# button.net
KiCad netlist of a schematic drawn in EAGLE
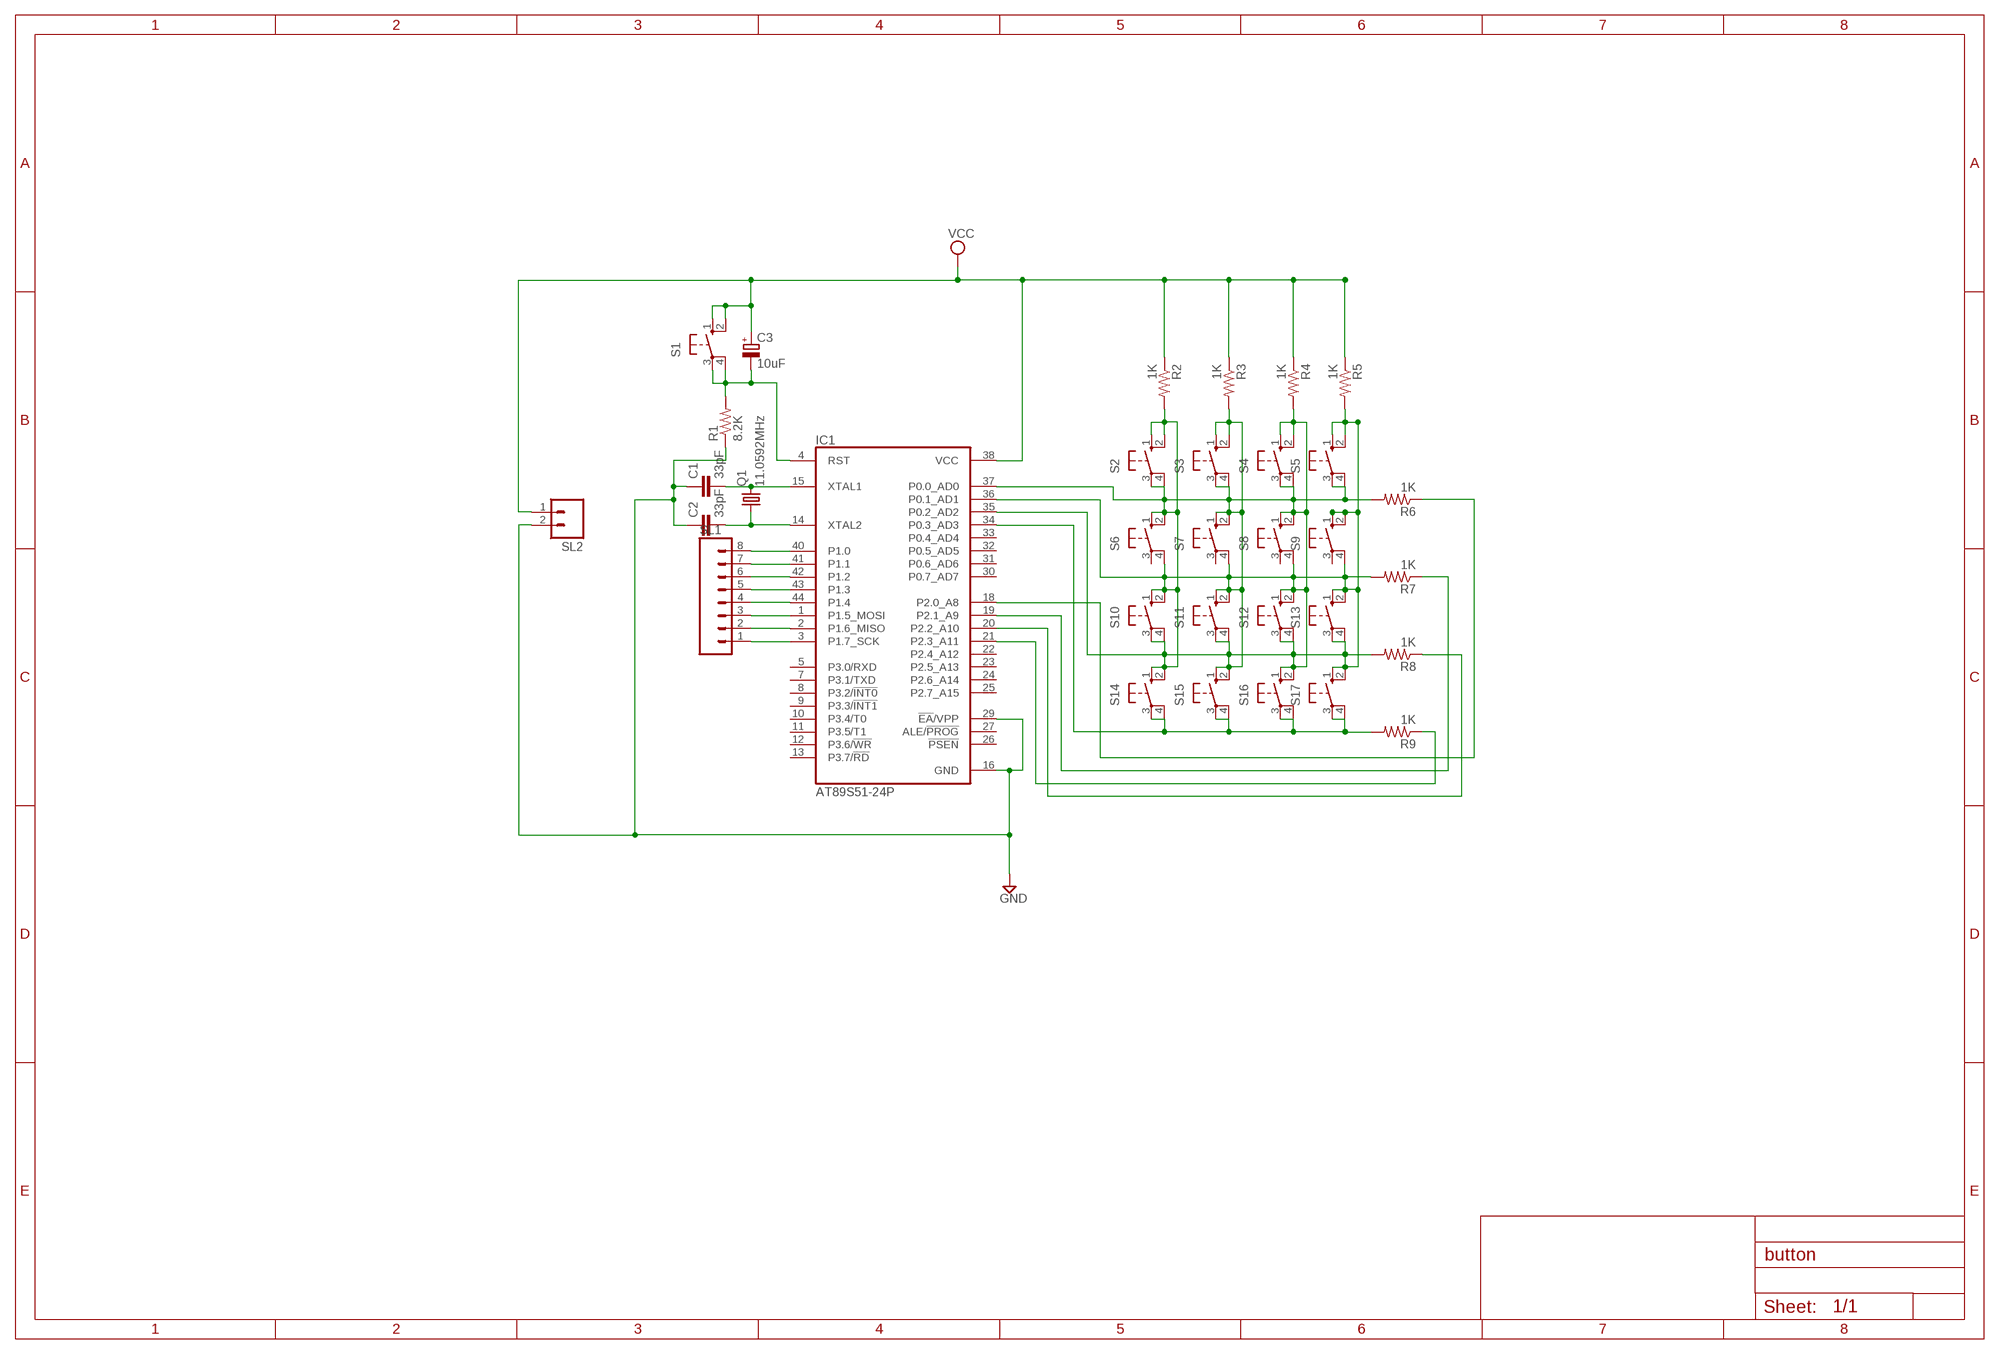
[diagram p0: schematic, sheet 1]

(export (version "E")
  (design (tool "Eeschema 10.0.6"))
  (components
    (comp (ref "C1")
      (value "33pF")
      (footprint "eagle-import:C1206K")
      (libsource (lib "eagle-import") (part "C-EUC1206K"))
    )
    (comp (ref "C2")
      (value "33pF")
      (footprint "eagle-import:C1206K")
      (libsource (lib "eagle-import") (part "C-EUC1206K"))
    )
    (comp (ref "C3")
      (value "10uF")
      (footprint "eagle-import:140CLH-1010")
      (libsource (lib "eagle-import") (part "CPOL-EU140CLH-1010"))
    )
    (comp (ref "IC1")
      (value "AT89S51-24P")
      (footprint "eagle-import:TQFP44")
      (libsource (lib "eagle-import") (part "AT89S51P-24"))
    )
    (comp (ref "Q1")
      (value "11.0592MHz")
      (footprint "eagle-import:TC26V")
      (libsource (lib "eagle-import") (part "CRYSTALTC26V"))
    )
    (comp (ref "R1")
      (value "8.2K")
      (footprint "eagle-import:R1206")
      (libsource (lib "eagle-import") (part "R-US_R1206"))
    )
    (comp (ref "R2")
      (value "1K")
      (footprint "eagle-import:M1206")
      (libsource (lib "eagle-import") (part "R-US_M1206"))
    )
    (comp (ref "R3")
      (value "1K")
      (footprint "eagle-import:M1206")
      (libsource (lib "eagle-import") (part "R-US_M1206"))
    )
    (comp (ref "R4")
      (value "1K")
      (footprint "eagle-import:M1206")
      (libsource (lib "eagle-import") (part "R-US_M1206"))
    )
    (comp (ref "R5")
      (value "1K")
      (footprint "eagle-import:M1206")
      (libsource (lib "eagle-import") (part "R-US_M1206"))
    )
    (comp (ref "R6")
      (value "1K")
      (footprint "eagle-import:M1206")
      (libsource (lib "eagle-import") (part "R-US_M1206"))
    )
    (comp (ref "R7")
      (value "1K")
      (footprint "eagle-import:M1206")
      (libsource (lib "eagle-import") (part "R-US_M1206"))
    )
    (comp (ref "R8")
      (value "1K")
      (footprint "eagle-import:M1206")
      (libsource (lib "eagle-import") (part "R-US_M1206"))
    )
    (comp (ref "R9")
      (value "1K")
      (footprint "eagle-import:M1206")
      (libsource (lib "eagle-import") (part "R-US_M1206"))
    )
    (comp (ref "S1")
      (value "10-XX")
      (footprint "eagle-import:B3F-10XX")
      (fields (field (name "MPN") "B3F-1000"))
      (libsource (lib "eagle-import") (part "10-XX"))
    )
    (comp (ref "S2")
      (value "10-XX")
      (footprint "eagle-import:B3F-10XX")
      (fields (field (name "MPN") "B3F-1000"))
      (libsource (lib "eagle-import") (part "10-XX"))
    )
    (comp (ref "S3")
      (value "10-XX")
      (footprint "eagle-import:B3F-10XX")
      (fields (field (name "MPN") "B3F-1000"))
      (libsource (lib "eagle-import") (part "10-XX"))
    )
    (comp (ref "S4")
      (value "10-XX")
      (footprint "eagle-import:B3F-10XX")
      (fields (field (name "MPN") "B3F-1000"))
      (libsource (lib "eagle-import") (part "10-XX"))
    )
    (comp (ref "S5")
      (value "10-XX")
      (footprint "eagle-import:B3F-10XX")
      (fields (field (name "MPN") "B3F-1000"))
      (libsource (lib "eagle-import") (part "10-XX"))
    )
    (comp (ref "S6")
      (value "10-XX")
      (footprint "eagle-import:B3F-10XX")
      (fields (field (name "MPN") "B3F-1000"))
      (libsource (lib "eagle-import") (part "10-XX"))
    )
    (comp (ref "S7")
      (value "10-XX")
      (footprint "eagle-import:B3F-10XX")
      (fields (field (name "MPN") "B3F-1000"))
      (libsource (lib "eagle-import") (part "10-XX"))
    )
    (comp (ref "S8")
      (value "10-XX")
      (footprint "eagle-import:B3F-10XX")
      (fields (field (name "MPN") "B3F-1000"))
      (libsource (lib "eagle-import") (part "10-XX"))
    )
    (comp (ref "S9")
      (value "10-XX")
      (footprint "eagle-import:B3F-10XX")
      (fields (field (name "MPN") "B3F-1000"))
      (libsource (lib "eagle-import") (part "10-XX"))
    )
    (comp (ref "S10")
      (value "10-XX")
      (footprint "eagle-import:B3F-10XX")
      (fields (field (name "MPN") "B3F-1000"))
      (libsource (lib "eagle-import") (part "10-XX"))
    )
    (comp (ref "S11")
      (value "10-XX")
      (footprint "eagle-import:B3F-10XX")
      (fields (field (name "MPN") "B3F-1000"))
      (libsource (lib "eagle-import") (part "10-XX"))
    )
    (comp (ref "S12")
      (value "10-XX")
      (footprint "eagle-import:B3F-10XX")
      (fields (field (name "MPN") "B3F-1000"))
      (libsource (lib "eagle-import") (part "10-XX"))
    )
    (comp (ref "S13")
      (value "10-XX")
      (footprint "eagle-import:B3F-10XX")
      (fields (field (name "MPN") "B3F-1000"))
      (libsource (lib "eagle-import") (part "10-XX"))
    )
    (comp (ref "S14")
      (value "10-XX")
      (footprint "eagle-import:B3F-10XX")
      (fields (field (name "MPN") "B3F-1000"))
      (libsource (lib "eagle-import") (part "10-XX"))
    )
    (comp (ref "S15")
      (value "10-XX")
      (footprint "eagle-import:B3F-10XX")
      (fields (field (name "MPN") "B3F-1000"))
      (libsource (lib "eagle-import") (part "10-XX"))
    )
    (comp (ref "S16")
      (value "10-XX")
      (footprint "eagle-import:B3F-10XX")
      (fields (field (name "MPN") "B3F-1000"))
      (libsource (lib "eagle-import") (part "10-XX"))
    )
    (comp (ref "S17")
      (value "10-XX")
      (footprint "eagle-import:B3F-10XX")
      (fields (field (name "MPN") "B3F-1000"))
      (libsource (lib "eagle-import") (part "10-XX"))
    )
    (comp (ref "SL1")
      (value "MA08")
      (footprint "eagle-import:08PA")
      (libsource (lib "eagle-import") (part "MA08"))
    )
    (comp (ref "SL2")
      (value "MA02")
      (footprint "eagle-import:02PA")
      (libsource (lib "eagle-import") (part "MA02"))
    )
  )
  (nets
    (net (code "1") (name "GND") (class "Default")
      (node (ref "C1") (pin "1") (pinfunction "1_1") (pintype "passive"))
      (node (ref "C2") (pin "1") (pinfunction "1_1") (pintype "passive"))
      (node (ref "IC1") (pin "16") (pinfunction "GND_16") (pintype "power_in"))
      (node (ref "IC1") (pin "29") (pinfunction "~{EA}/VPP_29") (pintype "input"))
      (node (ref "R1") (pin "1") (pinfunction "1_1") (pintype "passive"))
      (node (ref "SL2") (pin "2") (pinfunction "2_2") (pintype "passive"))
    )
    (net (code "2") (name "Net-(IC1A-P0.0_AD0)") (class "Default")
      (node (ref "IC1") (pin "35") (pinfunction "P0.2_AD2_35") (pintype "bidirectional"))
      (node (ref "IC1") (pin "36") (pinfunction "P0.1_AD1_36") (pintype "bidirectional"))
      (node (ref "IC1") (pin "37") (pinfunction "P0.0_AD0_37") (pintype "bidirectional"))
      (node (ref "R2") (pin "2") (pinfunction "2_2") (pintype "passive"))
      (node (ref "R3") (pin "2") (pinfunction "2_2") (pintype "passive"))
      (node (ref "R4") (pin "2") (pinfunction "2_2") (pintype "passive"))
      (node (ref "R5") (pin "2") (pinfunction "2_2") (pintype "passive"))
      (node (ref "R6") (pin "2") (pinfunction "2_2") (pintype "passive"))
      (node (ref "R7") (pin "2") (pinfunction "2_2") (pintype "passive"))
      (node (ref "R8") (pin "2") (pinfunction "2_2") (pintype "passive"))
      (node (ref "S10") (pin "1") (pinfunction "S_1") (pintype "passive"))
      (node (ref "S10") (pin "2") (pinfunction "S1_2") (pintype "passive"))
      (node (ref "S10") (pin "3") (pinfunction "P_3") (pintype "passive"))
      (node (ref "S10") (pin "4") (pinfunction "P1_4") (pintype "passive"))
      (node (ref "S11") (pin "1") (pinfunction "S_1") (pintype "passive"))
      (node (ref "S11") (pin "2") (pinfunction "S1_2") (pintype "passive"))
      (node (ref "S11") (pin "3") (pinfunction "P_3") (pintype "passive"))
      (node (ref "S11") (pin "4") (pinfunction "P1_4") (pintype "passive"))
      (node (ref "S12") (pin "1") (pinfunction "S_1") (pintype "passive"))
      (node (ref "S12") (pin "2") (pinfunction "S1_2") (pintype "passive"))
      (node (ref "S12") (pin "3") (pinfunction "P_3") (pintype "passive"))
      (node (ref "S12") (pin "4") (pinfunction "P1_4") (pintype "passive"))
      (node (ref "S13") (pin "1") (pinfunction "S_1") (pintype "passive"))
      (node (ref "S13") (pin "2") (pinfunction "S1_2") (pintype "passive"))
      (node (ref "S13") (pin "3") (pinfunction "P_3") (pintype "passive"))
      (node (ref "S13") (pin "4") (pinfunction "P1_4") (pintype "passive"))
      (node (ref "S14") (pin "1") (pinfunction "S_1") (pintype "passive"))
      (node (ref "S14") (pin "2") (pinfunction "S1_2") (pintype "passive"))
      (node (ref "S15") (pin "1") (pinfunction "S_1") (pintype "passive"))
      (node (ref "S15") (pin "2") (pinfunction "S1_2") (pintype "passive"))
      (node (ref "S16") (pin "1") (pinfunction "S_1") (pintype "passive"))
      (node (ref "S16") (pin "2") (pinfunction "S1_2") (pintype "passive"))
      (node (ref "S17") (pin "1") (pinfunction "S_1") (pintype "passive"))
      (node (ref "S17") (pin "2") (pinfunction "S1_2") (pintype "passive"))
      (node (ref "S2") (pin "1") (pinfunction "S_1") (pintype "passive"))
      (node (ref "S2") (pin "2") (pinfunction "S1_2") (pintype "passive"))
      (node (ref "S2") (pin "3") (pinfunction "P_3") (pintype "passive"))
      (node (ref "S2") (pin "4") (pinfunction "P1_4") (pintype "passive"))
      (node (ref "S3") (pin "1") (pinfunction "S_1") (pintype "passive"))
      (node (ref "S3") (pin "2") (pinfunction "S1_2") (pintype "passive"))
      (node (ref "S3") (pin "3") (pinfunction "P_3") (pintype "passive"))
      (node (ref "S3") (pin "4") (pinfunction "P1_4") (pintype "passive"))
      (node (ref "S4") (pin "1") (pinfunction "S_1") (pintype "passive"))
      (node (ref "S4") (pin "2") (pinfunction "S1_2") (pintype "passive"))
      (node (ref "S4") (pin "3") (pinfunction "P_3") (pintype "passive"))
      (node (ref "S4") (pin "4") (pinfunction "P1_4") (pintype "passive"))
      (node (ref "S5") (pin "1") (pinfunction "S_1") (pintype "passive"))
      (node (ref "S5") (pin "2") (pinfunction "S1_2") (pintype "passive"))
      (node (ref "S5") (pin "3") (pinfunction "P_3") (pintype "passive"))
      (node (ref "S5") (pin "4") (pinfunction "P1_4") (pintype "passive"))
      (node (ref "S6") (pin "1") (pinfunction "S_1") (pintype "passive"))
      (node (ref "S6") (pin "2") (pinfunction "S1_2") (pintype "passive"))
      (node (ref "S6") (pin "4") (pinfunction "P1_4") (pintype "passive"))
      (node (ref "S7") (pin "1") (pinfunction "S_1") (pintype "passive"))
      (node (ref "S7") (pin "2") (pinfunction "S1_2") (pintype "passive"))
      (node (ref "S7") (pin "4") (pinfunction "P1_4") (pintype "passive"))
      (node (ref "S8") (pin "1") (pinfunction "S_1") (pintype "passive"))
      (node (ref "S8") (pin "2") (pinfunction "S1_2") (pintype "passive"))
      (node (ref "S8") (pin "4") (pinfunction "P1_4") (pintype "passive"))
      (node (ref "S9") (pin "1") (pinfunction "S_1") (pintype "passive"))
      (node (ref "S9") (pin "2") (pinfunction "S1_2") (pintype "passive"))
      (node (ref "S9") (pin "4") (pinfunction "P1_4") (pintype "passive"))
    )
    (net (code "3") (name "Net-(IC1A-P0.3_AD3)") (class "Default")
      (node (ref "IC1") (pin "34") (pinfunction "P0.3_AD3_34") (pintype "bidirectional"))
      (node (ref "R9") (pin "2") (pinfunction "2_2") (pintype "passive"))
      (node (ref "S14") (pin "3") (pinfunction "P_3") (pintype "passive"))
      (node (ref "S14") (pin "4") (pinfunction "P1_4") (pintype "passive"))
      (node (ref "S15") (pin "3") (pinfunction "P_3") (pintype "passive"))
      (node (ref "S15") (pin "4") (pinfunction "P1_4") (pintype "passive"))
      (node (ref "S16") (pin "3") (pinfunction "P_3") (pintype "passive"))
      (node (ref "S16") (pin "4") (pinfunction "P1_4") (pintype "passive"))
      (node (ref "S17") (pin "3") (pinfunction "P_3") (pintype "passive"))
      (node (ref "S17") (pin "4") (pinfunction "P1_4") (pintype "passive"))
    )
    (net (code "4") (name "Net-(IC1A-P1.0)") (class "Default")
      (node (ref "IC1") (pin "40") (pinfunction "P1.0_40") (pintype "bidirectional"))
      (node (ref "SL1") (pin "8") (pinfunction "8_8") (pintype "passive"))
    )
    (net (code "5") (name "Net-(IC1A-P1.1)") (class "Default")
      (node (ref "IC1") (pin "41") (pinfunction "P1.1_41") (pintype "bidirectional"))
      (node (ref "SL1") (pin "7") (pinfunction "7_7") (pintype "passive"))
    )
    (net (code "6") (name "Net-(IC1A-P1.2)") (class "Default")
      (node (ref "IC1") (pin "42") (pinfunction "P1.2_42") (pintype "bidirectional"))
      (node (ref "SL1") (pin "6") (pinfunction "6_6") (pintype "passive"))
    )
    (net (code "7") (name "Net-(IC1A-P1.3)") (class "Default")
      (node (ref "IC1") (pin "43") (pinfunction "P1.3_43") (pintype "bidirectional"))
      (node (ref "SL1") (pin "5") (pinfunction "5_5") (pintype "passive"))
    )
    (net (code "8") (name "Net-(IC1A-P1.4)") (class "Default")
      (node (ref "IC1") (pin "44") (pinfunction "P1.4_44") (pintype "bidirectional"))
      (node (ref "SL1") (pin "4") (pinfunction "4_4") (pintype "passive"))
    )
    (net (code "9") (name "Net-(IC1A-P1.5_MOSI)") (class "Default")
      (node (ref "IC1") (pin "1") (pinfunction "P1.5_MOSI_1") (pintype "bidirectional"))
      (node (ref "SL1") (pin "3") (pinfunction "3_3") (pintype "passive"))
    )
    (net (code "10") (name "Net-(IC1A-P1.6_MISO)") (class "Default")
      (node (ref "IC1") (pin "2") (pinfunction "P1.6_MISO_2") (pintype "bidirectional"))
      (node (ref "SL1") (pin "2") (pinfunction "2_2") (pintype "passive"))
    )
    (net (code "11") (name "Net-(IC1A-P1.7_SCK)") (class "Default")
      (node (ref "IC1") (pin "3") (pinfunction "P1.7_SCK_3") (pintype "bidirectional"))
      (node (ref "SL1") (pin "1") (pinfunction "1_1") (pintype "passive"))
    )
    (net (code "12") (name "Net-(IC1A-P2.0_A8)") (class "Default")
      (node (ref "IC1") (pin "18") (pinfunction "P2.0_A8_18") (pintype "bidirectional"))
      (node (ref "R6") (pin "1") (pinfunction "1_1") (pintype "passive"))
    )
    (net (code "13") (name "Net-(IC1A-P2.1_A9)") (class "Default")
      (node (ref "IC1") (pin "19") (pinfunction "P2.1_A9_19") (pintype "bidirectional"))
      (node (ref "R7") (pin "1") (pinfunction "1_1") (pintype "passive"))
    )
    (net (code "14") (name "Net-(IC1A-P2.2_A10)") (class "Default")
      (node (ref "IC1") (pin "20") (pinfunction "P2.2_A10_20") (pintype "bidirectional"))
      (node (ref "R8") (pin "1") (pinfunction "1_1") (pintype "passive"))
    )
    (net (code "15") (name "Net-(IC1A-P2.3_A11)") (class "Default")
      (node (ref "IC1") (pin "21") (pinfunction "P2.3_A11_21") (pintype "bidirectional"))
      (node (ref "R9") (pin "1") (pinfunction "1_1") (pintype "passive"))
    )
    (net (code "16") (name "Net-(IC1A-RST)") (class "Default")
      (node (ref "C3") (pin "-") (pinfunction "-_-") (pintype "passive"))
      (node (ref "IC1") (pin "4") (pinfunction "RST_4") (pintype "input"))
      (node (ref "R1") (pin "2") (pinfunction "2_2") (pintype "passive"))
      (node (ref "S1") (pin "3") (pinfunction "P_3") (pintype "passive"))
      (node (ref "S1") (pin "4") (pinfunction "P1_4") (pintype "passive"))
    )
    (net (code "17") (name "Net-(IC1A-XTAL1)") (class "Default")
      (node (ref "C1") (pin "2") (pinfunction "2_2") (pintype "passive"))
      (node (ref "IC1") (pin "15") (pinfunction "XTAL1_15") (pintype "input"))
      (node (ref "Q1") (pin "2") (pinfunction "2_2") (pintype "passive"))
    )
    (net (code "18") (name "Net-(IC1A-XTAL2)") (class "Default")
      (node (ref "C2") (pin "2") (pinfunction "2_2") (pintype "passive"))
      (node (ref "IC1") (pin "14") (pinfunction "XTAL2_14") (pintype "input"))
      (node (ref "Q1") (pin "1") (pinfunction "1_1") (pintype "passive"))
    )
    (net (code "19") (name "VCC") (class "Default")
      (node (ref "C3") (pin "+") (pinfunction "+_+") (pintype "passive"))
      (node (ref "IC1") (pin "38") (pinfunction "VCC_38") (pintype "power_in"))
      (node (ref "R2") (pin "1") (pinfunction "1_1") (pintype "passive"))
      (node (ref "R3") (pin "1") (pinfunction "1_1") (pintype "passive"))
      (node (ref "R4") (pin "1") (pinfunction "1_1") (pintype "passive"))
      (node (ref "R5") (pin "1") (pinfunction "1_1") (pintype "passive"))
      (node (ref "S1") (pin "1") (pinfunction "S_1") (pintype "passive"))
      (node (ref "S1") (pin "2") (pinfunction "S1_2") (pintype "passive"))
      (node (ref "SL2") (pin "1") (pinfunction "1_1") (pintype "passive"))
    )
    (net (code "20") (name "unconnected-(IC1A-ALE{slash}~{PROG}-Pad27)") (class "Default")
      (node (ref "IC1") (pin "27") (pinfunction "ALE/~{PROG}_27") (pintype "output"))
    )
    (net (code "21") (name "unconnected-(IC1A-P0.4_AD4-Pad33)") (class "Default")
      (node (ref "IC1") (pin "33") (pinfunction "P0.4_AD4_33") (pintype "bidirectional"))
    )
    (net (code "22") (name "unconnected-(IC1A-P0.5_AD5-Pad32)") (class "Default")
      (node (ref "IC1") (pin "32") (pinfunction "P0.5_AD5_32") (pintype "bidirectional"))
    )
    (net (code "23") (name "unconnected-(IC1A-P0.6_AD6-Pad31)") (class "Default")
      (node (ref "IC1") (pin "31") (pinfunction "P0.6_AD6_31") (pintype "bidirectional"))
    )
    (net (code "24") (name "unconnected-(IC1A-P0.7_AD7-Pad30)") (class "Default")
      (node (ref "IC1") (pin "30") (pinfunction "P0.7_AD7_30") (pintype "bidirectional"))
    )
    (net (code "25") (name "unconnected-(IC1A-P2.4_A12-Pad22)") (class "Default")
      (node (ref "IC1") (pin "22") (pinfunction "P2.4_A12_22") (pintype "bidirectional"))
    )
    (net (code "26") (name "unconnected-(IC1A-P2.5_A13-Pad23)") (class "Default")
      (node (ref "IC1") (pin "23") (pinfunction "P2.5_A13_23") (pintype "bidirectional"))
    )
    (net (code "27") (name "unconnected-(IC1A-P2.6_A14-Pad24)") (class "Default")
      (node (ref "IC1") (pin "24") (pinfunction "P2.6_A14_24") (pintype "bidirectional"))
    )
    (net (code "28") (name "unconnected-(IC1A-P2.7_A15-Pad25)") (class "Default")
      (node (ref "IC1") (pin "25") (pinfunction "P2.7_A15_25") (pintype "bidirectional"))
    )
    (net (code "29") (name "unconnected-(IC1A-P3.0{slash}RXD-Pad5)") (class "Default")
      (node (ref "IC1") (pin "5") (pinfunction "P3.0/RXD_5") (pintype "bidirectional"))
    )
    (net (code "30") (name "unconnected-(IC1A-P3.1{slash}TXD-Pad7)") (class "Default")
      (node (ref "IC1") (pin "7") (pinfunction "P3.1/TXD_7") (pintype "bidirectional"))
    )
    (net (code "31") (name "unconnected-(IC1A-P3.2{slash}~{INT0}-Pad8)") (class "Default")
      (node (ref "IC1") (pin "8") (pinfunction "P3.2/~{INT0}_8") (pintype "bidirectional"))
    )
    (net (code "32") (name "unconnected-(IC1A-P3.3{slash}~{INT1}-Pad9)") (class "Default")
      (node (ref "IC1") (pin "9") (pinfunction "P3.3/~{INT1}_9") (pintype "bidirectional"))
    )
    (net (code "33") (name "unconnected-(IC1A-P3.4{slash}T0-Pad10)") (class "Default")
      (node (ref "IC1") (pin "10") (pinfunction "P3.4/T0_10") (pintype "bidirectional"))
    )
    (net (code "34") (name "unconnected-(IC1A-P3.5{slash}T1-Pad11)") (class "Default")
      (node (ref "IC1") (pin "11") (pinfunction "P3.5/T1_11") (pintype "bidirectional"))
    )
    (net (code "35") (name "unconnected-(IC1A-P3.6{slash}~{WR}-Pad12)") (class "Default")
      (node (ref "IC1") (pin "12") (pinfunction "P3.6/~{WR}_12") (pintype "bidirectional"))
    )
    (net (code "36") (name "unconnected-(IC1A-P3.7{slash}~{RD}-Pad13)") (class "Default")
      (node (ref "IC1") (pin "13") (pinfunction "P3.7/~{RD}_13") (pintype "bidirectional"))
    )
    (net (code "37") (name "unconnected-(IC1A-~{PSEN}-Pad26)") (class "Default")
      (node (ref "IC1") (pin "26") (pinfunction "~{PSEN}_26") (pintype "output"))
    )
    (net (code "38") (name "unconnected-(S6-P-Pad3)") (class "Default")
      (node (ref "S6") (pin "3") (pinfunction "P_3") (pintype "passive"))
    )
    (net (code "39") (name "unconnected-(S7-P-Pad3)") (class "Default")
      (node (ref "S7") (pin "3") (pinfunction "P_3") (pintype "passive"))
    )
    (net (code "40") (name "unconnected-(S8-P-Pad3)") (class "Default")
      (node (ref "S8") (pin "3") (pinfunction "P_3") (pintype "passive"))
    )
    (net (code "41") (name "unconnected-(S9-P-Pad3)") (class "Default")
      (node (ref "S9") (pin "3") (pinfunction "P_3") (pintype "passive"))
    )
  )
)
